# Body_PCB_v1.net
KiCad netlist of a schematic drawn in EAGLE
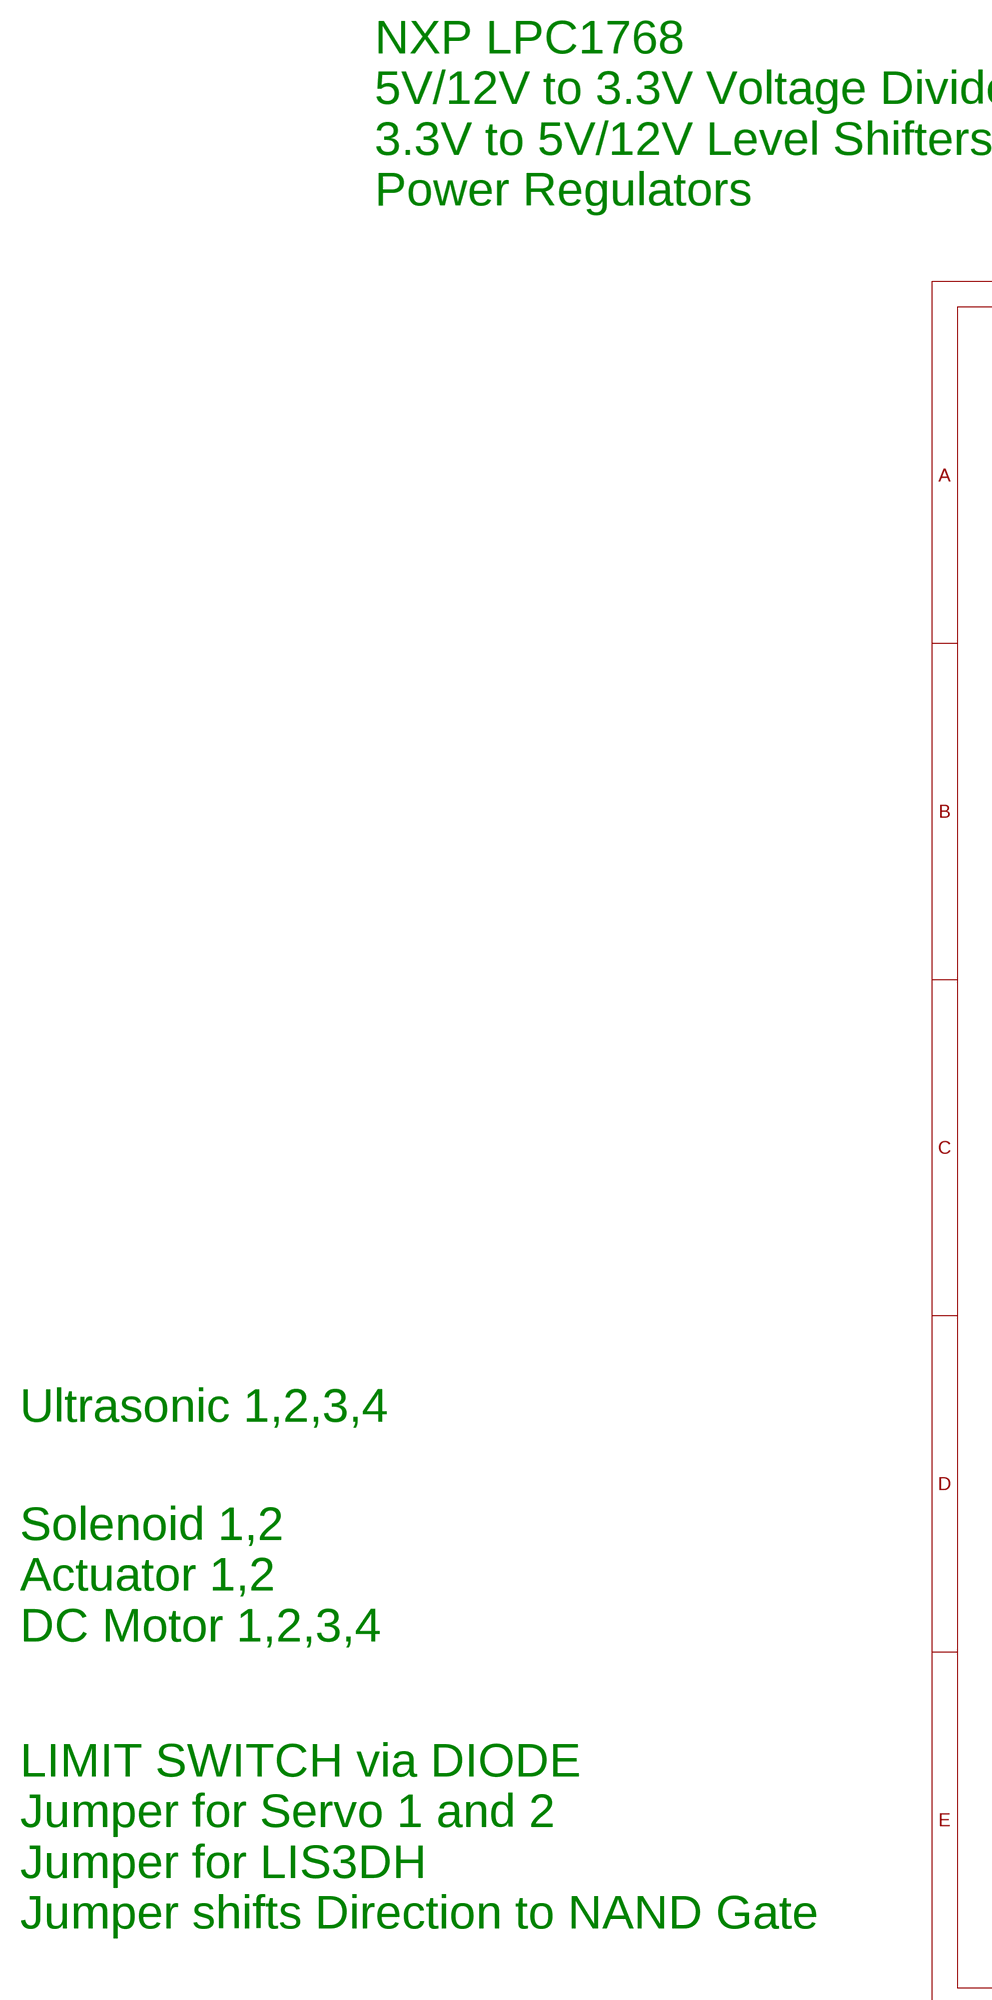
[diagram p0: schematic, sheet 1, part 1 of 2]
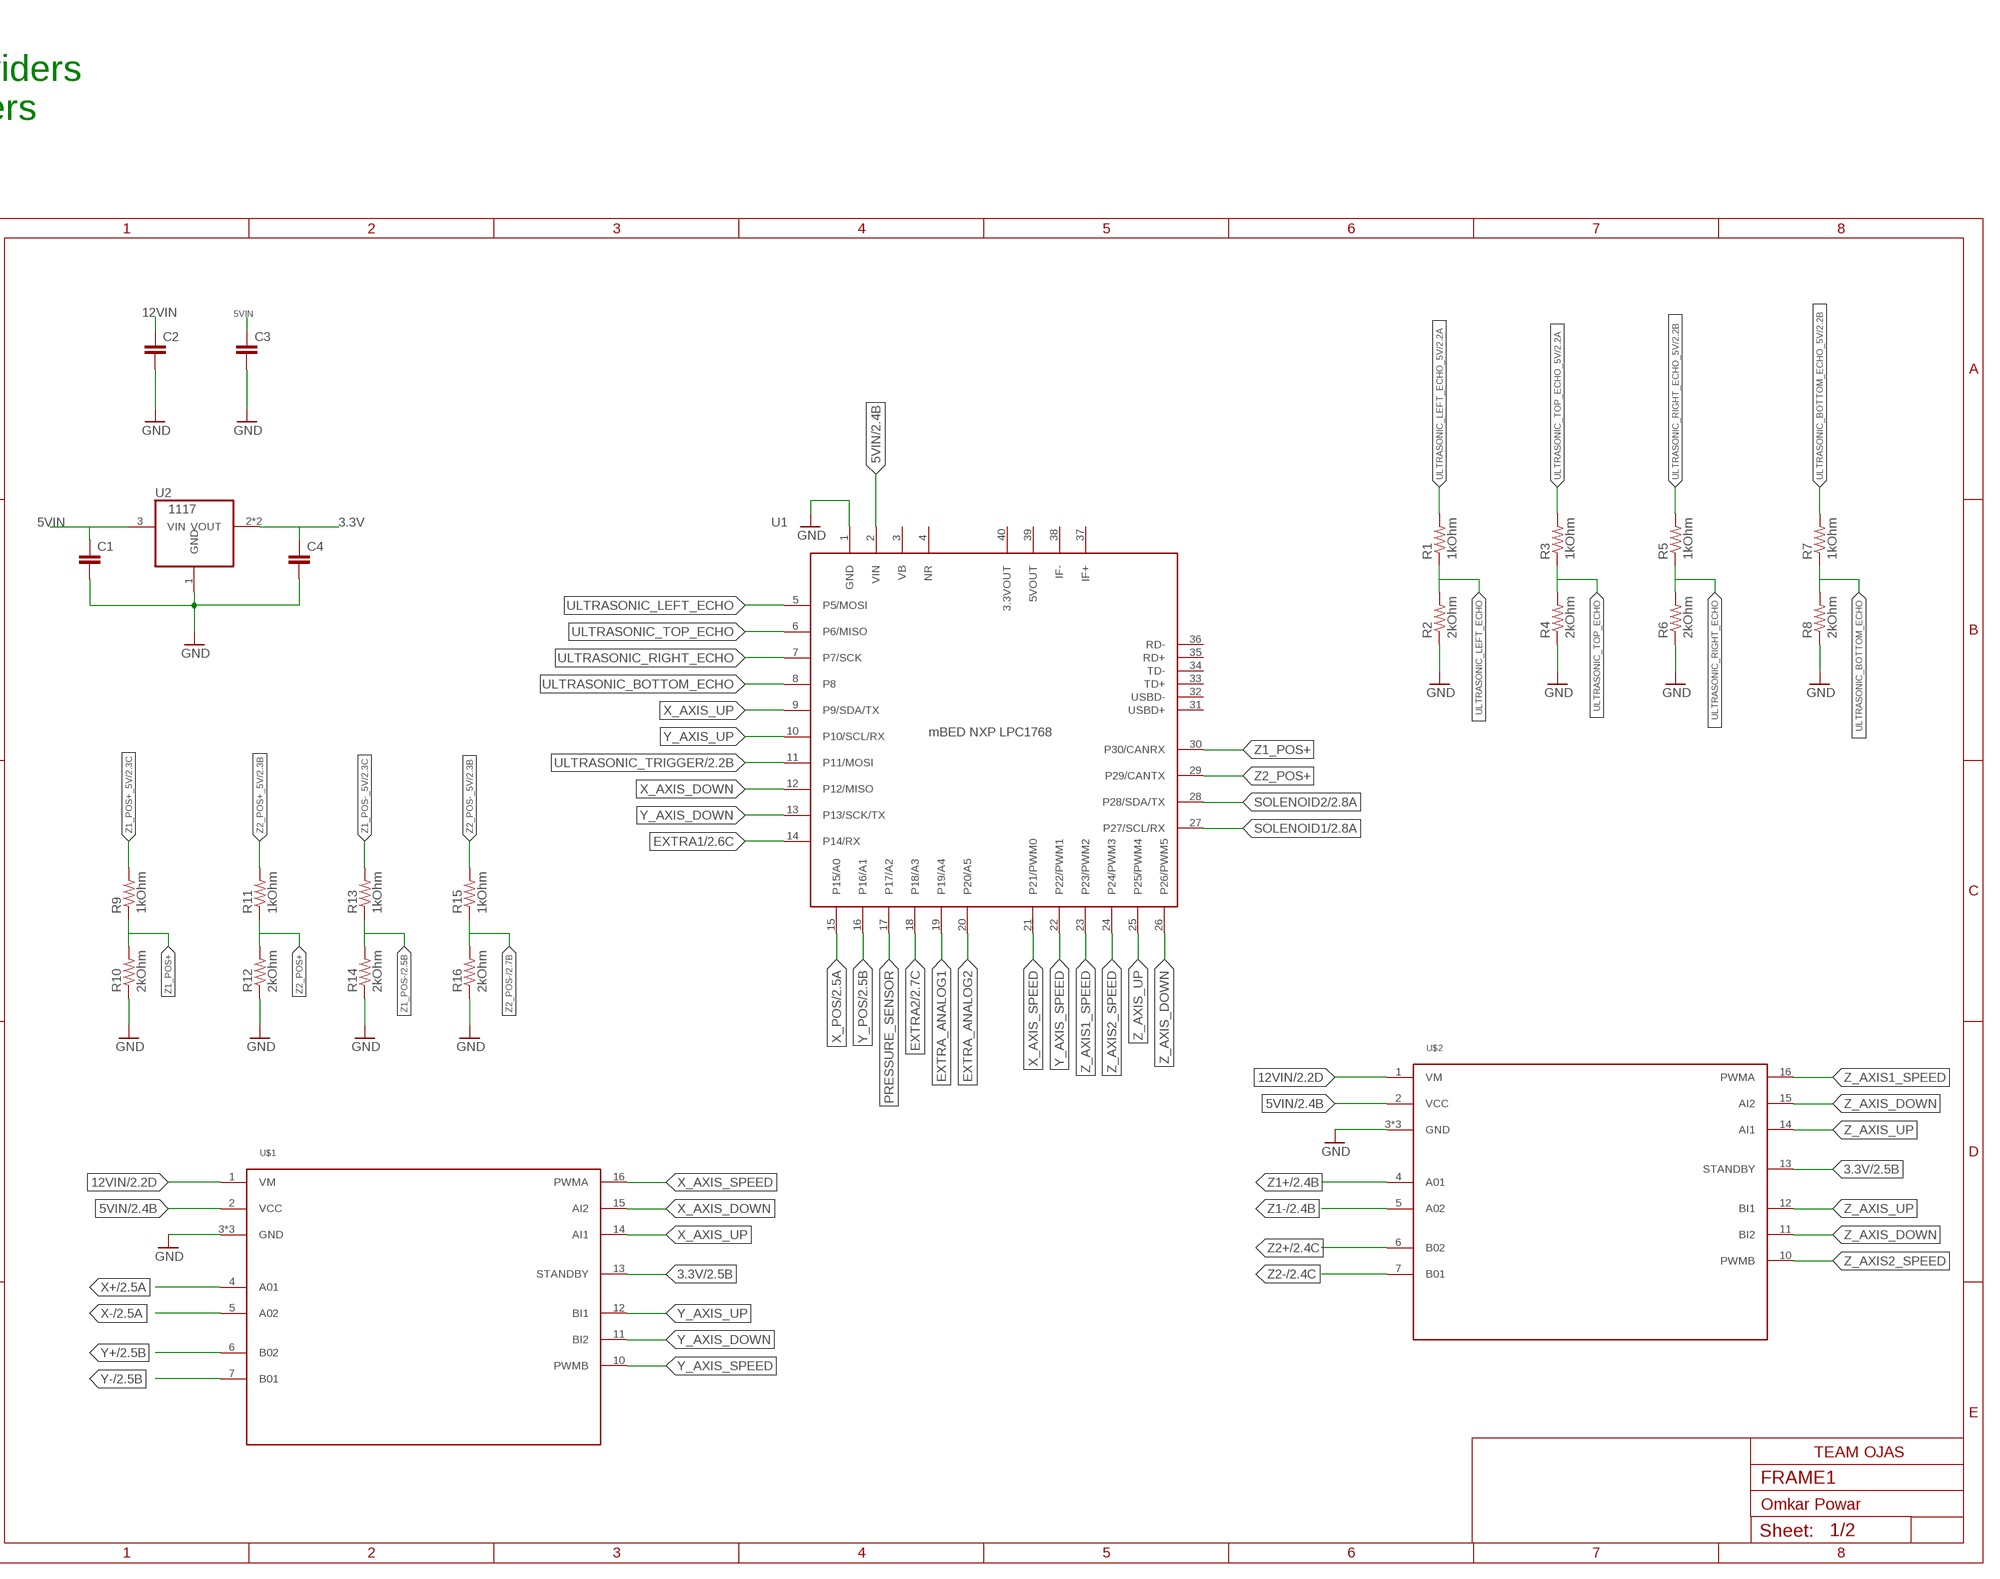
[diagram p1: schematic, sheet 1, part 2 of 2]
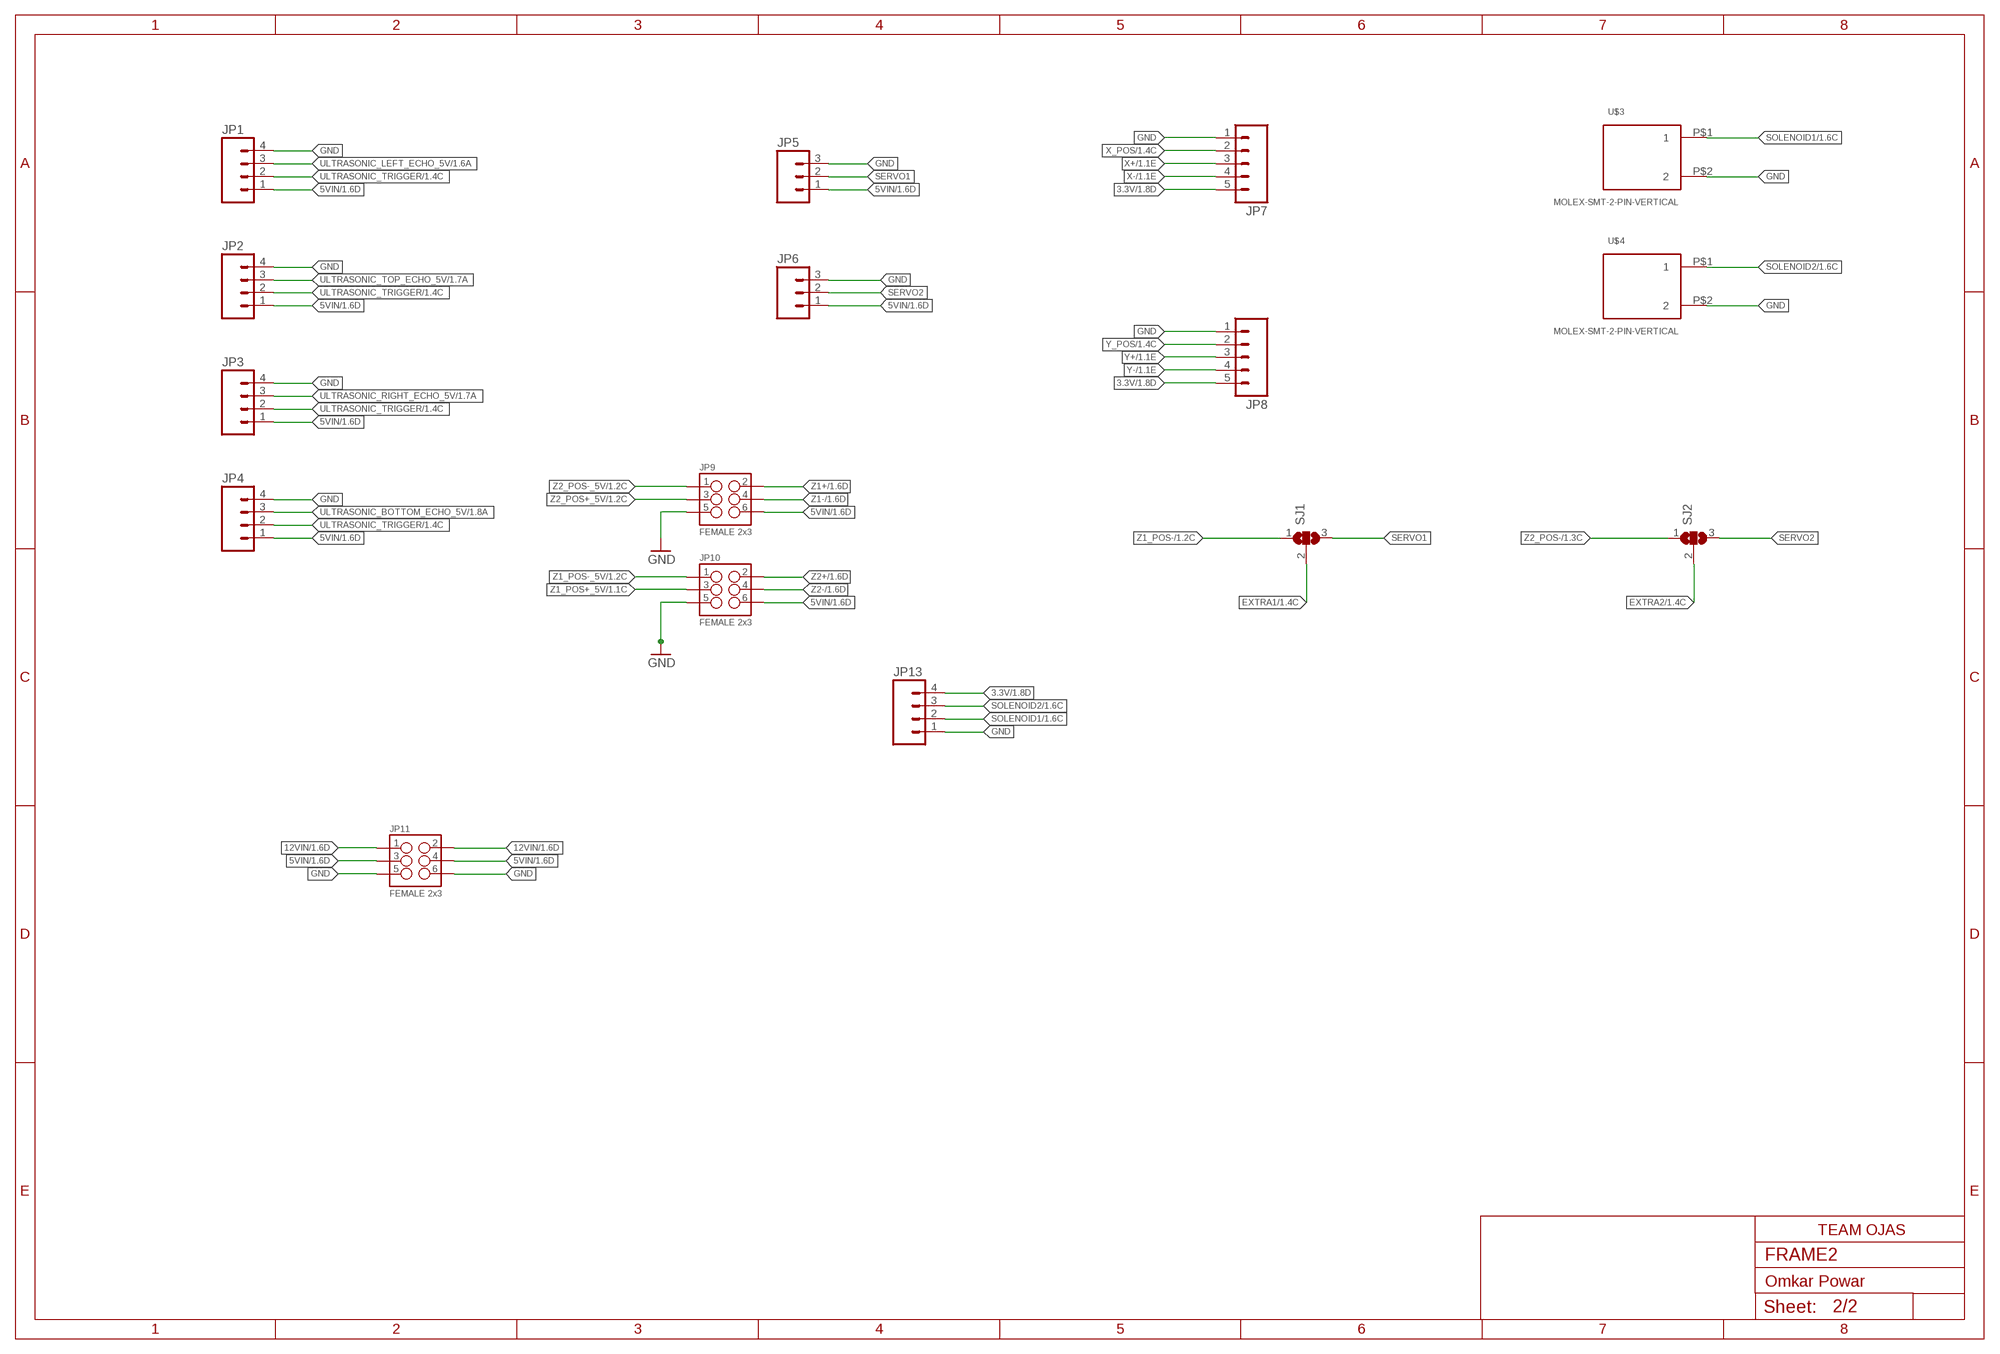
[diagram p2: schematic, sheet 2]

(export (version "E")
  (design (tool "Eeschema 10.0.6"))
  (components
    (comp (ref "JP1")
      (value "M04PTH")
      (footprint "eagle-import:1X04")
      (libsource (lib "eagle-import") (part "M04PTH"))
    )
    (comp (ref "JP2")
      (value "M04PTH")
      (footprint "eagle-import:1X04")
      (libsource (lib "eagle-import") (part "M04PTH"))
    )
    (comp (ref "JP3")
      (value "M04PTH")
      (footprint "eagle-import:1X04")
      (libsource (lib "eagle-import") (part "M04PTH"))
    )
    (comp (ref "JP4")
      (value "M04PTH")
      (footprint "eagle-import:1X04")
      (libsource (lib "eagle-import") (part "M04PTH"))
    )
    (comp (ref "JP5")
      (value "M03PTH")
      (footprint "eagle-import:1X03")
      (libsource (lib "eagle-import") (part "M03PTH"))
    )
    (comp (ref "JP6")
      (value "M03PTH")
      (footprint "eagle-import:1X03")
      (libsource (lib "eagle-import") (part "M03PTH"))
    )
    (comp (ref "JP7")
      (value "M05PTH")
      (footprint "eagle-import:1X05")
      (libsource (lib "eagle-import") (part "M05PTH"))
    )
    (comp (ref "JP8")
      (value "M05PTH")
      (footprint "eagle-import:1X05")
      (libsource (lib "eagle-import") (part "M05PTH"))
    )
    (comp (ref "JP9")
      (value "FEMALE 2x3")
      (footprint "eagle-import:2X3")
      (libsource (lib "eagle-import") (part "M03X2FEMALE"))
    )
    (comp (ref "JP10")
      (value "FEMALE 2x3")
      (footprint "eagle-import:2X3")
      (libsource (lib "eagle-import") (part "M03X2FEMALE"))
    )
    (comp (ref "JP11")
      (value "FEMALE 2x3")
      (footprint "eagle-import:2X3")
      (libsource (lib "eagle-import") (part "M03X2FEMALE"))
    )
    (comp (ref "JP13")
      (value "M04PTH")
      (footprint "eagle-import:1X04")
      (libsource (lib "eagle-import") (part "M04PTH"))
    )
    (comp (ref "SJ1")
      (value "SJ2W")
      (footprint "eagle-import:SJ_2")
      (libsource (lib "eagle-import") (part "SJ2W"))
    )
    (comp (ref "SJ2")
      (value "SJ2W")
      (footprint "eagle-import:SJ_2")
      (libsource (lib "eagle-import") (part "SJ2W"))
    )
    (comp (ref "U$3")
      (value "MOLEX-SMT-2-PIN-VERTICAL")
      (footprint "eagle-import:430450215")
      (libsource (lib "eagle-import") (part "MOLEX-SMT-2-PIN-VERTICAL"))
    )
    (comp (ref "U$4")
      (value "MOLEX-SMT-2-PIN-VERTICAL")
      (footprint "eagle-import:430450215")
      (libsource (lib "eagle-import") (part "MOLEX-SMT-2-PIN-VERTICAL"))
    )
    (comp (ref "C1")
      (value "C1206")
      (footprint "eagle-import:1206")
      (libsource (lib "eagle-import") (part "C1206"))
    )
    (comp (ref "C2")
      (value "C1206")
      (footprint "eagle-import:1206")
      (libsource (lib "eagle-import") (part "C1206"))
    )
    (comp (ref "C3")
      (value "C1206")
      (footprint "eagle-import:1206")
      (libsource (lib "eagle-import") (part "C1206"))
    )
    (comp (ref "C4")
      (value "C1206")
      (footprint "eagle-import:1206")
      (libsource (lib "eagle-import") (part "C1206"))
    )
    (comp (ref "R1")
      (value "1kOhm")
      (footprint "eagle-import:0805")
      (libsource (lib "eagle-import") (part "Team_Ojas_OVPowar_R0805"))
    )
    (comp (ref "R2")
      (value "2kOhm")
      (footprint "eagle-import:0805")
      (libsource (lib "eagle-import") (part "Team_Ojas_OVPowar_R0805"))
    )
    (comp (ref "R3")
      (value "1kOhm")
      (footprint "eagle-import:0805")
      (libsource (lib "eagle-import") (part "Team_Ojas_OVPowar_R0805"))
    )
    (comp (ref "R4")
      (value "2kOhm")
      (footprint "eagle-import:0805")
      (libsource (lib "eagle-import") (part "Team_Ojas_OVPowar_R0805"))
    )
    (comp (ref "R5")
      (value "1kOhm")
      (footprint "eagle-import:0805")
      (libsource (lib "eagle-import") (part "Team_Ojas_OVPowar_R0805"))
    )
    (comp (ref "R6")
      (value "2kOhm")
      (footprint "eagle-import:0805")
      (libsource (lib "eagle-import") (part "Team_Ojas_OVPowar_R0805"))
    )
    (comp (ref "R7")
      (value "1kOhm")
      (footprint "eagle-import:0805")
      (libsource (lib "eagle-import") (part "Team_Ojas_OVPowar_R0805"))
    )
    (comp (ref "R8")
      (value "2kOhm")
      (footprint "eagle-import:0805")
      (libsource (lib "eagle-import") (part "Team_Ojas_OVPowar_R0805"))
    )
    (comp (ref "R9")
      (value "1kOhm")
      (footprint "eagle-import:0805")
      (libsource (lib "eagle-import") (part "Team_Ojas_OVPowar_R0805"))
    )
    (comp (ref "R10")
      (value "2kOhm")
      (footprint "eagle-import:0805")
      (libsource (lib "eagle-import") (part "Team_Ojas_OVPowar_R0805"))
    )
    (comp (ref "R11")
      (value "1kOhm")
      (footprint "eagle-import:0805")
      (libsource (lib "eagle-import") (part "Team_Ojas_OVPowar_R0805"))
    )
    (comp (ref "R12")
      (value "2kOhm")
      (footprint "eagle-import:0805")
      (libsource (lib "eagle-import") (part "Team_Ojas_OVPowar_R0805"))
    )
    (comp (ref "R13")
      (value "1kOhm")
      (footprint "eagle-import:0805")
      (libsource (lib "eagle-import") (part "Team_Ojas_OVPowar_R0805"))
    )
    (comp (ref "R14")
      (value "2kOhm")
      (footprint "eagle-import:0805")
      (libsource (lib "eagle-import") (part "Team_Ojas_OVPowar_R0805"))
    )
    (comp (ref "R15")
      (value "1kOhm")
      (footprint "eagle-import:0805")
      (libsource (lib "eagle-import") (part "Team_Ojas_OVPowar_R0805"))
    )
    (comp (ref "R16")
      (value "2kOhm")
      (footprint "eagle-import:0805")
      (libsource (lib "eagle-import") (part "Team_Ojas_OVPowar_R0805"))
    )
    (comp (ref "U$1")
      (value "TB6612FNG")
      (footprint "eagle-import:TB6612FNG_DRIVER")
      (libsource (lib "eagle-import") (part "TB6612FNG"))
    )
    (comp (ref "U$2")
      (value "TB6612FNG")
      (footprint "eagle-import:TB6612FNG_DRIVER")
      (libsource (lib "eagle-import") (part "TB6612FNG"))
    )
    (comp (ref "U1")
      (value "MBED_NXP_LPC1768")
      (footprint "eagle-import:40_PDIP")
      (libsource (lib "eagle-import") (part "MBED_NXP_LPC1768"))
    )
    (comp (ref "U2")
      (value "1117")
      (footprint "eagle-import:SOT223")
      (libsource (lib "eagle-import") (part "Carnot_AfterMarket_v2.2_1117"))
    )
  )
  (nets
    (net (code "1") (name "3.3V") (class "Default")
      (node (ref "C4") (pin "1") (pinfunction "1_1") (pintype "passive"))
      (node (ref "JP13") (pin "4") (pinfunction "4_4") (pintype "passive"))
      (node (ref "JP7") (pin "5") (pinfunction "5_5") (pintype "passive"))
      (node (ref "JP8") (pin "5") (pinfunction "5_5") (pintype "passive"))
      (node (ref "U$1") (pin "13") (pinfunction "STANDBY_13") (pintype "bidirectional"))
      (node (ref "U$2") (pin "13") (pinfunction "STANDBY_13") (pintype "bidirectional"))
      (node (ref "U2") (pin "2") (pinfunction "VOUT_2") (pintype "output"))
      (node (ref "U2") (pin "4") (pinfunction "VOUT_4") (pintype "output"))
    )
    (net (code "2") (name "5VIN") (class "Default")
      (node (ref "C1") (pin "1") (pinfunction "1_1") (pintype "passive"))
      (node (ref "C3") (pin "1") (pinfunction "1_1") (pintype "passive"))
      (node (ref "JP1") (pin "1") (pinfunction "1_1") (pintype "passive"))
      (node (ref "JP10") (pin "6") (pinfunction "6_6") (pintype "bidirectional"))
      (node (ref "JP11") (pin "3") (pinfunction "3_3") (pintype "bidirectional"))
      (node (ref "JP11") (pin "4") (pinfunction "4_4") (pintype "bidirectional"))
      (node (ref "JP2") (pin "1") (pinfunction "1_1") (pintype "passive"))
      (node (ref "JP3") (pin "1") (pinfunction "1_1") (pintype "passive"))
      (node (ref "JP4") (pin "1") (pinfunction "1_1") (pintype "passive"))
      (node (ref "JP5") (pin "1") (pinfunction "1_1") (pintype "passive"))
      (node (ref "JP6") (pin "1") (pinfunction "1_1") (pintype "passive"))
      (node (ref "JP9") (pin "6") (pinfunction "6_6") (pintype "bidirectional"))
      (node (ref "U$1") (pin "2") (pinfunction "VCC_2") (pintype "bidirectional"))
      (node (ref "U$2") (pin "2") (pinfunction "VCC_2") (pintype "bidirectional"))
      (node (ref "U1") (pin "2") (pinfunction "VIN_2") (pintype "bidirectional"))
      (node (ref "U2") (pin "3") (pinfunction "VIN_3") (pintype "input"))
    )
    (net (code "3") (name "12VIN") (class "Default")
      (node (ref "C2") (pin "1") (pinfunction "1_1") (pintype "passive"))
      (node (ref "JP11") (pin "1") (pinfunction "1_1") (pintype "bidirectional"))
      (node (ref "JP11") (pin "2") (pinfunction "2_2") (pintype "bidirectional"))
      (node (ref "U$1") (pin "1") (pinfunction "VM_1") (pintype "bidirectional"))
      (node (ref "U$2") (pin "1") (pinfunction "VM_1") (pintype "bidirectional"))
    )
    (net (code "4") (name "EXTRA1") (class "Default")
      (node (ref "SJ1") (pin "2") (pinfunction "2_2") (pintype "passive"))
      (node (ref "U1") (pin "14") (pinfunction "P14/RX_14") (pintype "bidirectional"))
    )
    (net (code "5") (name "EXTRA2") (class "Default")
      (node (ref "SJ2") (pin "2") (pinfunction "2_2") (pintype "passive"))
      (node (ref "U1") (pin "18") (pinfunction "P18/A3_18") (pintype "bidirectional"))
    )
    (net (code "6") (name "EXTRA_ANALOG1") (class "Default")
      (node (ref "U1") (pin "19") (pinfunction "P19/A4_19") (pintype "bidirectional"))
    )
    (net (code "7") (name "EXTRA_ANALOG2") (class "Default")
      (node (ref "U1") (pin "20") (pinfunction "P20/A5_20") (pintype "bidirectional"))
    )
    (net (code "8") (name "GND") (class "Default")
      (node (ref "C1") (pin "2") (pinfunction "2_2") (pintype "passive"))
      (node (ref "C2") (pin "2") (pinfunction "2_2") (pintype "passive"))
      (node (ref "C3") (pin "2") (pinfunction "2_2") (pintype "passive"))
      (node (ref "C4") (pin "2") (pinfunction "2_2") (pintype "passive"))
      (node (ref "JP1") (pin "4") (pinfunction "4_4") (pintype "passive"))
      (node (ref "JP10") (pin "5") (pinfunction "5_5") (pintype "bidirectional"))
      (node (ref "JP11") (pin "5") (pinfunction "5_5") (pintype "bidirectional"))
      (node (ref "JP11") (pin "6") (pinfunction "6_6") (pintype "bidirectional"))
      (node (ref "JP13") (pin "1") (pinfunction "1_1") (pintype "passive"))
      (node (ref "JP2") (pin "4") (pinfunction "4_4") (pintype "passive"))
      (node (ref "JP3") (pin "4") (pinfunction "4_4") (pintype "passive"))
      (node (ref "JP4") (pin "4") (pinfunction "4_4") (pintype "passive"))
      (node (ref "JP5") (pin "3") (pinfunction "3_3") (pintype "passive"))
      (node (ref "JP6") (pin "3") (pinfunction "3_3") (pintype "passive"))
      (node (ref "JP7") (pin "1") (pinfunction "1_1") (pintype "passive"))
      (node (ref "JP8") (pin "1") (pinfunction "1_1") (pintype "passive"))
      (node (ref "JP9") (pin "5") (pinfunction "5_5") (pintype "bidirectional"))
      (node (ref "R10") (pin "P$1") (pinfunction "1_P$1") (pintype "passive"))
      (node (ref "R12") (pin "P$1") (pinfunction "1_P$1") (pintype "passive"))
      (node (ref "R14") (pin "P$1") (pinfunction "1_P$1") (pintype "passive"))
      (node (ref "R16") (pin "P$1") (pinfunction "1_P$1") (pintype "passive"))
      (node (ref "R2") (pin "P$1") (pinfunction "1_P$1") (pintype "passive"))
      (node (ref "R4") (pin "P$1") (pinfunction "1_P$1") (pintype "passive"))
      (node (ref "R6") (pin "P$1") (pinfunction "1_P$1") (pintype "passive"))
      (node (ref "R8") (pin "P$1") (pinfunction "1_P$1") (pintype "passive"))
      (node (ref "U$1") (pin "3") (pinfunction "GND_3") (pintype "bidirectional"))
      (node (ref "U$1") (pin "8") (pinfunction "GND_8") (pintype "bidirectional"))
      (node (ref "U$1") (pin "9") (pinfunction "GND_9") (pintype "bidirectional"))
      (node (ref "U$2") (pin "3") (pinfunction "GND_3") (pintype "bidirectional"))
      (node (ref "U$2") (pin "8") (pinfunction "GND_8") (pintype "bidirectional"))
      (node (ref "U$2") (pin "9") (pinfunction "GND_9") (pintype "bidirectional"))
      (node (ref "U$3") (pin "P$2") (pinfunction "2_P$2") (pintype "bidirectional"))
      (node (ref "U$4") (pin "P$2") (pinfunction "2_P$2") (pintype "bidirectional"))
      (node (ref "U1") (pin "1") (pinfunction "GND_1") (pintype "bidirectional"))
      (node (ref "U2") (pin "1") (pinfunction "GND_1") (pintype "power_in"))
    )
    (net (code "9") (name "PRESSURE_SENSOR") (class "Default")
      (node (ref "U1") (pin "17") (pinfunction "P17/A2_17") (pintype "bidirectional"))
    )
    (net (code "10") (name "SERVO1") (class "Default")
      (node (ref "JP5") (pin "2") (pinfunction "2_2") (pintype "passive"))
      (node (ref "SJ1") (pin "3") (pinfunction "3_3") (pintype "passive"))
    )
    (net (code "11") (name "SERVO2") (class "Default")
      (node (ref "JP6") (pin "2") (pinfunction "2_2") (pintype "passive"))
      (node (ref "SJ2") (pin "3") (pinfunction "3_3") (pintype "passive"))
    )
    (net (code "12") (name "SOLENOID1") (class "Default")
      (node (ref "JP13") (pin "2") (pinfunction "2_2") (pintype "passive"))
      (node (ref "U$3") (pin "P$1") (pinfunction "1_P$1") (pintype "bidirectional"))
      (node (ref "U1") (pin "27") (pinfunction "P27/SCL/RX_27") (pintype "bidirectional"))
    )
    (net (code "13") (name "SOLENOID2") (class "Default")
      (node (ref "JP13") (pin "3") (pinfunction "3_3") (pintype "passive"))
      (node (ref "U$4") (pin "P$1") (pinfunction "1_P$1") (pintype "bidirectional"))
      (node (ref "U1") (pin "28") (pinfunction "P28/SDA/TX_28") (pintype "bidirectional"))
    )
    (net (code "14") (name "ULTRASONIC_BOTTOM_ECHO") (class "Default")
      (node (ref "R7") (pin "P$1") (pinfunction "1_P$1") (pintype "passive"))
      (node (ref "R8") (pin "P$2") (pinfunction "2_P$2") (pintype "passive"))
      (node (ref "U1") (pin "8") (pinfunction "P8_8") (pintype "bidirectional"))
    )
    (net (code "15") (name "ULTRASONIC_BOTTOM_ECHO_5V") (class "Default")
      (node (ref "JP4") (pin "3") (pinfunction "3_3") (pintype "passive"))
      (node (ref "R7") (pin "P$2") (pinfunction "2_P$2") (pintype "passive"))
    )
    (net (code "16") (name "ULTRASONIC_LEFT_ECHO") (class "Default")
      (node (ref "R1") (pin "P$1") (pinfunction "1_P$1") (pintype "passive"))
      (node (ref "R2") (pin "P$2") (pinfunction "2_P$2") (pintype "passive"))
      (node (ref "U1") (pin "5") (pinfunction "P5/MOSI_5") (pintype "bidirectional"))
    )
    (net (code "17") (name "ULTRASONIC_LEFT_ECHO_5V") (class "Default")
      (node (ref "JP1") (pin "3") (pinfunction "3_3") (pintype "passive"))
      (node (ref "R1") (pin "P$2") (pinfunction "2_P$2") (pintype "passive"))
    )
    (net (code "18") (name "ULTRASONIC_RIGHT_ECHO") (class "Default")
      (node (ref "R5") (pin "P$1") (pinfunction "1_P$1") (pintype "passive"))
      (node (ref "R6") (pin "P$2") (pinfunction "2_P$2") (pintype "passive"))
      (node (ref "U1") (pin "7") (pinfunction "P7/SCK_7") (pintype "bidirectional"))
    )
    (net (code "19") (name "ULTRASONIC_RIGHT_ECHO_5V") (class "Default")
      (node (ref "JP3") (pin "3") (pinfunction "3_3") (pintype "passive"))
      (node (ref "R5") (pin "P$2") (pinfunction "2_P$2") (pintype "passive"))
    )
    (net (code "20") (name "ULTRASONIC_TOP_ECHO") (class "Default")
      (node (ref "R3") (pin "P$1") (pinfunction "1_P$1") (pintype "passive"))
      (node (ref "R4") (pin "P$2") (pinfunction "2_P$2") (pintype "passive"))
      (node (ref "U1") (pin "6") (pinfunction "P6/MISO_6") (pintype "bidirectional"))
    )
    (net (code "21") (name "ULTRASONIC_TOP_ECHO_5V") (class "Default")
      (node (ref "JP2") (pin "3") (pinfunction "3_3") (pintype "passive"))
      (node (ref "R3") (pin "P$2") (pinfunction "2_P$2") (pintype "passive"))
    )
    (net (code "22") (name "ULTRASONIC_TRIGGER") (class "Default")
      (node (ref "JP1") (pin "2") (pinfunction "2_2") (pintype "passive"))
      (node (ref "JP2") (pin "2") (pinfunction "2_2") (pintype "passive"))
      (node (ref "JP3") (pin "2") (pinfunction "2_2") (pintype "passive"))
      (node (ref "JP4") (pin "2") (pinfunction "2_2") (pintype "passive"))
      (node (ref "U1") (pin "11") (pinfunction "P11/MOSI_11") (pintype "bidirectional"))
    )
    (net (code "23") (name "X+") (class "Default")
      (node (ref "JP7") (pin "3") (pinfunction "3_3") (pintype "passive"))
      (node (ref "U$1") (pin "4") (pinfunction "A01_4") (pintype "bidirectional"))
    )
    (net (code "24") (name "X-") (class "Default")
      (node (ref "JP7") (pin "4") (pinfunction "4_4") (pintype "passive"))
      (node (ref "U$1") (pin "5") (pinfunction "A02_5") (pintype "bidirectional"))
    )
    (net (code "25") (name "X_AXIS_DOWN") (class "Default")
      (node (ref "U$1") (pin "15") (pinfunction "AI2_15") (pintype "bidirectional"))
      (node (ref "U1") (pin "12") (pinfunction "P12/MISO_12") (pintype "bidirectional"))
    )
    (net (code "26") (name "X_AXIS_SPEED") (class "Default")
      (node (ref "U$1") (pin "16") (pinfunction "PWMA_16") (pintype "bidirectional"))
      (node (ref "U1") (pin "21") (pinfunction "P21/PWM0_21") (pintype "bidirectional"))
    )
    (net (code "27") (name "X_AXIS_UP") (class "Default")
      (node (ref "U$1") (pin "14") (pinfunction "AI1_14") (pintype "bidirectional"))
      (node (ref "U1") (pin "9") (pinfunction "P9/SDA/TX_9") (pintype "bidirectional"))
    )
    (net (code "28") (name "X_POS") (class "Default")
      (node (ref "JP7") (pin "2") (pinfunction "2_2") (pintype "passive"))
      (node (ref "U1") (pin "15") (pinfunction "P15/A0_15") (pintype "bidirectional"))
    )
    (net (code "29") (name "Y+") (class "Default")
      (node (ref "JP8") (pin "3") (pinfunction "3_3") (pintype "passive"))
      (node (ref "U$1") (pin "6") (pinfunction "B02_6") (pintype "bidirectional"))
    )
    (net (code "30") (name "Y-") (class "Default")
      (node (ref "JP8") (pin "4") (pinfunction "4_4") (pintype "passive"))
      (node (ref "U$1") (pin "7") (pinfunction "B01_7") (pintype "bidirectional"))
    )
    (net (code "31") (name "Y_AXIS_DOWN") (class "Default")
      (node (ref "U$1") (pin "11") (pinfunction "BI2_11") (pintype "bidirectional"))
      (node (ref "U1") (pin "13") (pinfunction "P13/SCK/TX_13") (pintype "bidirectional"))
    )
    (net (code "32") (name "Y_AXIS_SPEED") (class "Default")
      (node (ref "U$1") (pin "10") (pinfunction "PWMB_10") (pintype "bidirectional"))
      (node (ref "U1") (pin "22") (pinfunction "P22/PWM1_22") (pintype "bidirectional"))
    )
    (net (code "33") (name "Y_AXIS_UP") (class "Default")
      (node (ref "U$1") (pin "12") (pinfunction "BI1_12") (pintype "bidirectional"))
      (node (ref "U1") (pin "10") (pinfunction "P10/SCL/RX_10") (pintype "bidirectional"))
    )
    (net (code "34") (name "Y_POS") (class "Default")
      (node (ref "JP8") (pin "2") (pinfunction "2_2") (pintype "passive"))
      (node (ref "U1") (pin "16") (pinfunction "P16/A1_16") (pintype "bidirectional"))
    )
    (net (code "35") (name "Z1+") (class "Default")
      (node (ref "JP9") (pin "2") (pinfunction "2_2") (pintype "bidirectional"))
      (node (ref "U$2") (pin "4") (pinfunction "A01_4") (pintype "bidirectional"))
    )
    (net (code "36") (name "Z1-") (class "Default")
      (node (ref "JP9") (pin "4") (pinfunction "4_4") (pintype "bidirectional"))
      (node (ref "U$2") (pin "5") (pinfunction "A02_5") (pintype "bidirectional"))
    )
    (net (code "37") (name "Z1_POS+") (class "Default")
      (node (ref "R10") (pin "P$2") (pinfunction "2_P$2") (pintype "passive"))
      (node (ref "R9") (pin "P$1") (pinfunction "1_P$1") (pintype "passive"))
      (node (ref "U1") (pin "30") (pinfunction "P30/CANRX_30") (pintype "bidirectional"))
    )
    (net (code "38") (name "Z1_POS+_5V") (class "Default")
      (node (ref "JP10") (pin "3") (pinfunction "3_3") (pintype "bidirectional"))
      (node (ref "R9") (pin "P$2") (pinfunction "2_P$2") (pintype "passive"))
    )
    (net (code "39") (name "Z1_POS-") (class "Default")
      (node (ref "R13") (pin "P$1") (pinfunction "1_P$1") (pintype "passive"))
      (node (ref "R14") (pin "P$2") (pinfunction "2_P$2") (pintype "passive"))
      (node (ref "SJ1") (pin "1") (pinfunction "1_1") (pintype "passive"))
    )
    (net (code "40") (name "Z1_POS-_5V") (class "Default")
      (node (ref "JP10") (pin "1") (pinfunction "1_1") (pintype "bidirectional"))
      (node (ref "R13") (pin "P$2") (pinfunction "2_P$2") (pintype "passive"))
    )
    (net (code "41") (name "Z2+") (class "Default")
      (node (ref "JP10") (pin "2") (pinfunction "2_2") (pintype "bidirectional"))
      (node (ref "U$2") (pin "6") (pinfunction "B02_6") (pintype "bidirectional"))
    )
    (net (code "42") (name "Z2-") (class "Default")
      (node (ref "JP10") (pin "4") (pinfunction "4_4") (pintype "bidirectional"))
      (node (ref "U$2") (pin "7") (pinfunction "B01_7") (pintype "bidirectional"))
    )
    (net (code "43") (name "Z2_POS+") (class "Default")
      (node (ref "R11") (pin "P$1") (pinfunction "1_P$1") (pintype "passive"))
      (node (ref "R12") (pin "P$2") (pinfunction "2_P$2") (pintype "passive"))
      (node (ref "U1") (pin "29") (pinfunction "P29/CANTX_29") (pintype "bidirectional"))
    )
    (net (code "44") (name "Z2_POS+_5V") (class "Default")
      (node (ref "JP9") (pin "3") (pinfunction "3_3") (pintype "bidirectional"))
      (node (ref "R11") (pin "P$2") (pinfunction "2_P$2") (pintype "passive"))
    )
    (net (code "45") (name "Z2_POS-") (class "Default")
      (node (ref "R15") (pin "P$1") (pinfunction "1_P$1") (pintype "passive"))
      (node (ref "R16") (pin "P$2") (pinfunction "2_P$2") (pintype "passive"))
      (node (ref "SJ2") (pin "1") (pinfunction "1_1") (pintype "passive"))
    )
    (net (code "46") (name "Z2_POS-_5V") (class "Default")
      (node (ref "JP9") (pin "1") (pinfunction "1_1") (pintype "bidirectional"))
      (node (ref "R15") (pin "P$2") (pinfunction "2_P$2") (pintype "passive"))
    )
    (net (code "47") (name "Z_AXIS1_SPEED") (class "Default")
      (node (ref "U$2") (pin "16") (pinfunction "PWMA_16") (pintype "bidirectional"))
      (node (ref "U1") (pin "23") (pinfunction "P23/PWM2_23") (pintype "bidirectional"))
    )
    (net (code "48") (name "Z_AXIS2_SPEED") (class "Default")
      (node (ref "U$2") (pin "10") (pinfunction "PWMB_10") (pintype "bidirectional"))
      (node (ref "U1") (pin "24") (pinfunction "P24/PWM3_24") (pintype "bidirectional"))
    )
    (net (code "49") (name "Z_AXIS_DOWN") (class "Default")
      (node (ref "U$2") (pin "11") (pinfunction "BI2_11") (pintype "bidirectional"))
      (node (ref "U$2") (pin "15") (pinfunction "AI2_15") (pintype "bidirectional"))
      (node (ref "U1") (pin "26") (pinfunction "P26/PWM5_26") (pintype "bidirectional"))
    )
    (net (code "50") (name "Z_AXIS_UP") (class "Default")
      (node (ref "U$2") (pin "12") (pinfunction "BI1_12") (pintype "bidirectional"))
      (node (ref "U$2") (pin "14") (pinfunction "AI1_14") (pintype "bidirectional"))
      (node (ref "U1") (pin "25") (pinfunction "P25/PWM4_25") (pintype "bidirectional"))
    )
    (net (code "51") (name "unconnected-(U1-3.3VOUT-Pad40)") (class "Default")
      (node (ref "U1") (pin "40") (pinfunction "3.3VOUT_40") (pintype "bidirectional"))
    )
    (net (code "52") (name "unconnected-(U1-5VOUT-Pad39)") (class "Default")
      (node (ref "U1") (pin "39") (pinfunction "5VOUT_39") (pintype "bidirectional"))
    )
    (net (code "53") (name "unconnected-(U1-IF+-Pad37)") (class "Default")
      (node (ref "U1") (pin "37") (pinfunction "IF+_37") (pintype "bidirectional"))
    )
    (net (code "54") (name "unconnected-(U1-IF--Pad38)") (class "Default")
      (node (ref "U1") (pin "38") (pinfunction "IF-_38") (pintype "bidirectional"))
    )
    (net (code "55") (name "unconnected-(U1-NR-Pad4)") (class "Default")
      (node (ref "U1") (pin "4") (pinfunction "NR_4") (pintype "bidirectional"))
    )
    (net (code "56") (name "unconnected-(U1-RD+-Pad35)") (class "Default")
      (node (ref "U1") (pin "35") (pinfunction "RD+_35") (pintype "bidirectional"))
    )
    (net (code "57") (name "unconnected-(U1-RD--Pad36)") (class "Default")
      (node (ref "U1") (pin "36") (pinfunction "RD-_36") (pintype "bidirectional"))
    )
    (net (code "58") (name "unconnected-(U1-TD+-Pad33)") (class "Default")
      (node (ref "U1") (pin "33") (pinfunction "TD+_33") (pintype "bidirectional"))
    )
    (net (code "59") (name "unconnected-(U1-TD--Pad34)") (class "Default")
      (node (ref "U1") (pin "34") (pinfunction "TD-_34") (pintype "bidirectional"))
    )
    (net (code "60") (name "unconnected-(U1-USBD+-Pad31)") (class "Default")
      (node (ref "U1") (pin "31") (pinfunction "USBD+_31") (pintype "bidirectional"))
    )
    (net (code "61") (name "unconnected-(U1-USBD--Pad32)") (class "Default")
      (node (ref "U1") (pin "32") (pinfunction "USBD-_32") (pintype "bidirectional"))
    )
    (net (code "62") (name "unconnected-(U1-VB-Pad3)") (class "Default")
      (node (ref "U1") (pin "3") (pinfunction "VB_3") (pintype "bidirectional"))
    )
  )
)
